# Sheet1.net
KiCad netlist of a schematic drawn in Altium Designer
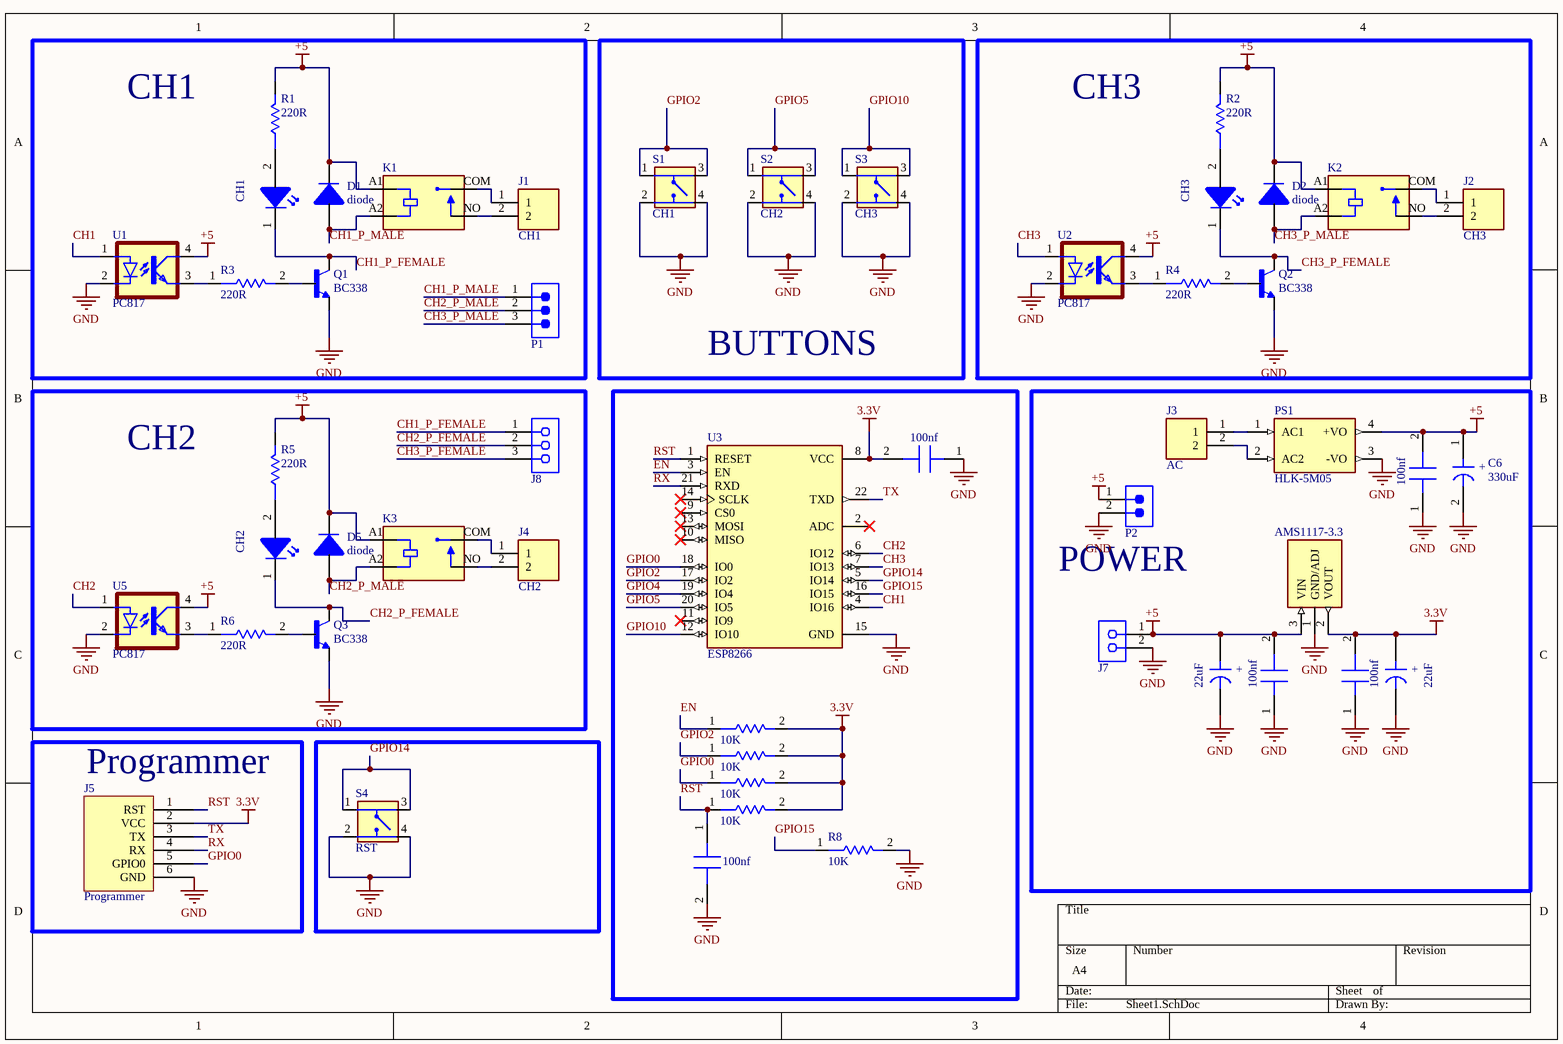
[diagram p0: Sheet1.SchDoc]

(export (version "E")
  (design (tool "Eeschema 10.0.6"))
  (components
    (comp (ref "C1")
      (value "100nf")
      (footprint "CL31B104KCFNNNE")
      (description "0.1 µF ±10% 100V Ceramic Capacitor X7R 1206 (3216 Metric)")
      (libsource (lib "Schlib1") (part "CL31B104KCFNNNE"))
    )
    (comp (ref "C4")
      (value "100nf")
      (footprint "CL31B104KCFNNNE")
      (description "0.1 µF ±10% 100V Ceramic Capacitor X7R 1206 (3216 Metric)")
      (libsource (lib "Schlib1") (part "CL31B104KCFNNNE"))
    )
    (comp (ref "C5")
      (value "100nf")
      (footprint "CL31B104KCFNNNE")
      (description "0.1 µF ±10% 100V Ceramic Capacitor X7R 1206 (3216 Metric)")
      (libsource (lib "Schlib1") (part "CL31B104KCFNNNE"))
    )
    (comp (ref "C6")
      (value "330uF")
      (footprint "UCL1V331MNL1GS")
      (description "330 µF 35 V Aluminum Electrolytic Capacitors Radial, Can - SMD 2000 Hrs @ 105°C")
      (libsource (lib "Schlib1") (part "UCL1V331MNL1GS"))
    )
    (comp (ref "C7")
      (value "100nf")
      (footprint "CL31B104KCFNNNE")
      (description "0.1 µF ±10% 100V Ceramic Capacitor X7R 1206 (3216 Metric)")
      (libsource (lib "Schlib1") (part "CL31B104KCFNNNE"))
    )
    (comp (ref "C8")
      (value "100nf")
      (footprint "CL31B104KCFNNNE")
      (description "0.1 µF ±10% 100V Ceramic Capacitor X7R 1206 (3216 Metric)")
      (libsource (lib "Schlib1") (part "CL31B104KCFNNNE"))
    )
    (comp (ref "C9")
      (value "22uF")
      (footprint "865060342002")
      (description "22 µF 16 V Aluminum Electrolytic Capacitors Radial, Can - SMD 2000 Hrs @ 105°C")
      (libsource (lib "Schlib1") (part "865060342002"))
    )
    (comp (ref "C10")
      (value "22uF")
      (footprint "865060342002")
      (description "22 µF 16 V Aluminum Electrolytic Capacitors Radial, Can - SMD 2000 Hrs @ 105°C")
      (libsource (lib "Schlib1") (part "865060342002"))
    )
    (comp (ref "D1")
      (value "diode")
      (footprint "1N4007W")
      (description "Diode 1000 V 1A Surface Mount SOD-123FL")
      (libsource (lib "Schlib1") (part "1N4007W"))
    )
    (comp (ref "D2")
      (value "diode")
      (footprint "1N4007W")
      (description "Diode 1000 V 1A Surface Mount SOD-123FL")
      (libsource (lib "Schlib1") (part "1N4007W"))
    )
    (comp (ref "D3")
      (value "CH1")
      (footprint "IN-S126ATR")
      (description "Red 622nm LED Indication - Discrete 2V 1206 (3216 Metric)")
      (libsource (lib "Schlib1") (part "IN-S126ATR"))
    )
    (comp (ref "D4")
      (value "CH3")
      (footprint "IN-S126ATR")
      (description "Red 622nm LED Indication - Discrete 2V 1206 (3216 Metric)")
      (libsource (lib "Schlib1") (part "IN-S126ATR"))
    )
    (comp (ref "D5")
      (value "diode")
      (footprint "1N4007W")
      (description "Diode 1000 V 1A Surface Mount SOD-123FL")
      (libsource (lib "Schlib1") (part "1N4007W"))
    )
    (comp (ref "D6")
      (value "CH2")
      (footprint "IN-S126ATR")
      (description "Red 622nm LED Indication - Discrete 2V 1206 (3216 Metric)")
      (libsource (lib "Schlib1") (part "IN-S126ATR"))
    )
    (comp (ref "J1")
      (value "CH1")
      (footprint "KF127-5.0-2P")
      (description "Connector, Terminal Block; Wire Receptacle; 2 Pos.; 16-30 AWG; 0.197 in. CL; Sid")
      (libsource (lib "Schlib1") (part "KF127-5.0-2P"))
    )
    (comp (ref "J2")
      (value "CH3")
      (footprint "KF127-5.0-2P")
      (description "Connector, Terminal Block; Wire Receptacle; 2 Pos.; 16-30 AWG; 0.197 in. CL; Sid")
      (libsource (lib "Schlib1") (part "KF127-5.0-2P"))
    )
    (comp (ref "J3")
      (value "AC")
      (footprint "KF127-5.0-2P")
      (description "Connector, Terminal Block; Wire Receptacle; 2 Pos.; 16-30 AWG; 0.197 in. CL; Sid")
      (libsource (lib "") (part "KF127-5.0-2P_1"))
    )
    (comp (ref "J4")
      (value "CH2")
      (footprint "KF127-5.0-2P")
      (description "Connector, Terminal Block; Wire Receptacle; 2 Pos.; 16-30 AWG; 0.197 in. CL; Sid")
      (libsource (lib "Schlib1") (part "KF127-5.0-2P"))
    )
    (comp (ref "J5")
      (value "Programmer")
      (footprint "PHT-106-XX-X-S")
      (description "6 pin male pin header")
      (libsource (lib "Schlib1") (part "PHT-106-XX-X-S"))
    )
    (comp (ref "J7")
      (value "61300211821")
      (footprint "61300211821")
      (description "WR-PHD Socket Header, THT, Vertical, pitch 2.54mm, 1 Row, 2P")
      (fields (field (name "MANUFACTURER") "Wurth Elektronik"))
      (libsource (lib "Altium_WR-PHD_rev24a") (part "61300211821"))
    )
    (comp (ref "J8")
      (value "61300311821")
      (footprint "61300311821")
      (description "WR-PHD Socket Header, THT, Vertical, pitch 2.54mm, 1 Row, 3P")
      (fields (field (name "MANUFACTURER") "Wurth Elektronik"))
      (libsource (lib "Altium_WR-PHD_rev24a") (part "61300311821"))
    )
    (comp (ref "K1")
      (value "PR8-5V-450-1A")
      (footprint "PR8-5V-450-1A")
      (description "18.2 x 10.2 x 15.5 mm, 5 V, 16 A, SPST (1 Form A), Power Relay")
      (libsource (lib "Schlib1") (part "PR8-5V-450-1A"))
    )
    (comp (ref "K2")
      (value "PR8-5V-450-1A")
      (footprint "PR8-5V-450-1A")
      (description "18.2 x 10.2 x 15.5 mm, 5 V, 16 A, SPST (1 Form A), Power Relay")
      (libsource (lib "Schlib1") (part "PR8-5V-450-1A"))
    )
    (comp (ref "K3")
      (value "PR8-5V-450-1A")
      (footprint "PR8-5V-450-1A")
      (description "18.2 x 10.2 x 15.5 mm, 5 V, 16 A, SPST (1 Form A), Power Relay")
      (libsource (lib "Schlib1") (part "PR8-5V-450-1A"))
    )
    (comp (ref "P1")
      (value "61300311121")
      (footprint "61300311121")
      (description "WR-PHD Pin Header, THT, Vertical, pitch 2.54mm, 1 Row, 3P")
      (fields (field (name "MANUFACTURER") "Wurth Elektronik"))
      (libsource (lib "Altium_WR-PHD_rev24a") (part "61300311121"))
    )
    (comp (ref "P2")
      (value "61300211121")
      (footprint "61300211121")
      (description "WR-PHD Pin Header, THT, Vertical, pitch 2.54mm, 1 Row, 2P")
      (fields (field (name "MANUFACTURER") "Wurth Elektronik"))
      (libsource (lib "Altium_WR-PHD_rev24a") (part "61300211121"))
    )
    (comp (ref "PS1")
      (value "HLK-5M05")
      (footprint "HLK-5M05")
      (description "AC DC 220V to 5V 5W 5Watt Isolated Switching Step-Down Power Supply Module Converter")
      (libsource (lib "Schlib1") (part "HLK-5M05"))
    )
    (comp (ref "Q1")
      (value "BC338")
      (footprint "BC338")
      (description "Bipolar (BJT) Transistor NPN 25 V 800 mA 100MHz 625 mW Through Hole TO-92-3")
      (libsource (lib "Schlib1") (part "BC338"))
    )
    (comp (ref "Q2")
      (value "BC338")
      (footprint "BC338")
      (description "Bipolar (BJT) Transistor NPN 25 V 800 mA 100MHz 625 mW Through Hole TO-92-3")
      (libsource (lib "Schlib1") (part "BC338"))
    )
    (comp (ref "Q3")
      (value "BC338")
      (footprint "BC338")
      (description "Bipolar (BJT) Transistor NPN 25 V 800 mA 100MHz 625 mW Through Hole TO-92-3")
      (libsource (lib "Schlib1") (part "BC338"))
    )
    (comp (ref "R1")
      (value "220R")
      (footprint "RMCF1206FT220R")
      (description "220 Ohms ±1% 0.25W, 1/4W Chip Resistor 1206 (3216 Metric) Automotive AEC-Q200 Thick Film")
      (libsource (lib "Schlib1") (part "RMCF1206FT220R"))
    )
    (comp (ref "R2")
      (value "220R")
      (footprint "RMCF1206FT220R")
      (description "220 Ohms ±1% 0.25W, 1/4W Chip Resistor 1206 (3216 Metric) Automotive AEC-Q200 Thick Film")
      (libsource (lib "Schlib1") (part "RMCF1206FT220R"))
    )
    (comp (ref "R3")
      (value "220R")
      (footprint "RMCF1206FT220R")
      (description "220 Ohms ±1% 0.25W, 1/4W Chip Resistor 1206 (3216 Metric) Automotive AEC-Q200 Thick Film")
      (libsource (lib "") (part "RMCF1206FT220R_1"))
    )
    (comp (ref "R4")
      (value "220R")
      (footprint "RMCF1206FT220R")
      (description "220 Ohms ±1% 0.25W, 1/4W Chip Resistor 1206 (3216 Metric) Automotive AEC-Q200 Thick Film")
      (libsource (lib "") (part "RMCF1206FT220R_1"))
    )
    (comp (ref "R5")
      (value "220R")
      (footprint "RMCF1206FT220R")
      (description "220 Ohms ±1% 0.25W, 1/4W Chip Resistor 1206 (3216 Metric) Automotive AEC-Q200 Thick Film")
      (libsource (lib "Schlib1") (part "RMCF1206FT220R"))
    )
    (comp (ref "R6")
      (value "220R")
      (footprint "RMCF1206FT220R")
      (description "220 Ohms ±1% 0.25W, 1/4W Chip Resistor 1206 (3216 Metric) Automotive AEC-Q200 Thick Film")
      (libsource (lib "") (part "RMCF1206FT220R_1"))
    )
    (comp (ref "R7")
      (value "10K")
      (footprint "RC1206FR-0710KL")
      (description "10 kOhms ±1% 0.25W, 1/4W Chip Resistor 1206 (3216 Metric) Moisture Resistant Thick Film")
      (libsource (lib "Schlib1") (part "RC1206FR-0710KL"))
    )
    (comp (ref "R8")
      (value "10K")
      (footprint "RC1206FR-0710KL")
      (description "10 kOhms ±1% 0.25W, 1/4W Chip Resistor 1206 (3216 Metric) Moisture Resistant Thick Film")
      (libsource (lib "Schlib1") (part "RC1206FR-0710KL"))
    )
    (comp (ref "R9")
      (value "10K")
      (footprint "RC1206FR-0710KL")
      (description "10 kOhms ±1% 0.25W, 1/4W Chip Resistor 1206 (3216 Metric) Moisture Resistant Thick Film")
      (libsource (lib "Schlib1") (part "RC1206FR-0710KL"))
    )
    (comp (ref "R11")
      (value "10K")
      (footprint "RC1206FR-0710KL")
      (description "10 kOhms ±1% 0.25W, 1/4W Chip Resistor 1206 (3216 Metric) Moisture Resistant Thick Film")
      (libsource (lib "Schlib1") (part "RC1206FR-0710KL"))
    )
    (comp (ref "R12")
      (value "10K")
      (footprint "RC1206FR-0710KL")
      (description "10 kOhms ±1% 0.25W, 1/4W Chip Resistor 1206 (3216 Metric) Moisture Resistant Thick Film")
      (libsource (lib "Schlib1") (part "RC1206FR-0710KL"))
    )
    (comp (ref "S1")
      (value "CH1")
      (footprint "FSM8JH")
      (description "Tactile Switch SPST-NO Top Actuated Through Hole")
      (libsource (lib "Schlib1") (part "FSM8JH"))
    )
    (comp (ref "S2")
      (value "CH2")
      (footprint "FSM8JH")
      (description "Tactile Switch SPST-NO Top Actuated Through Hole")
      (libsource (lib "Schlib1") (part "FSM8JH"))
    )
    (comp (ref "S3")
      (value "CH3")
      (footprint "FSM8JH")
      (description "Tactile Switch SPST-NO Top Actuated Through Hole")
      (libsource (lib "Schlib1") (part "FSM8JH"))
    )
    (comp (ref "S4")
      (value "RST")
      (footprint "FSM8JH")
      (description "Tactile Switch SPST-NO Top Actuated Through Hole")
      (libsource (lib "Schlib1") (part "FSM8JH"))
    )
    (comp (ref "U1")
      (value "PC817")
      (footprint "PC817X2NSZ9F")
      (description "Optoisolator Transistor Output 5000Vrms 1 Channel 4-DIP")
      (libsource (lib "Schlib1") (part "PC817X2NSZ9F"))
    )
    (comp (ref "U2")
      (value "PC817")
      (footprint "PC817X2NSZ9F")
      (description "Optoisolator Transistor Output 5000Vrms 1 Channel 4-DIP")
      (libsource (lib "Schlib1") (part "PC817X2NSZ9F"))
    )
    (comp (ref "U3")
      (value "ESP8266")
      (footprint "ESP8266-12-F")
      (libsource (lib "Schlib1") (part "ESP8266-12-F"))
    )
    (comp (ref "U4")
      (value "AMS1117-3.3")
      (footprint "AMS1117-3.3")
      (description "Sot223/Pkg 1-Amp 3.3-Volt Low Drop Out Voltage Regulatator")
      (libsource (lib "Schlib1") (part "AMS1117-3.3"))
    )
    (comp (ref "U5")
      (value "PC817")
      (footprint "PC817X2NSZ9F")
      (description "Optoisolator Transistor Output 5000Vrms 1 Channel 4-DIP")
      (libsource (lib "Schlib1") (part "PC817X2NSZ9F"))
    )
  )
  (nets
    (net (code "1") (name "+5") (class "Default")
      (node (ref "C5") (pin "2") (pinfunction "2_2") (pintype "passive"))
      (node (ref "C6") (pin "1") (pinfunction "1_1") (pintype "passive"))
      (node (ref "C7") (pin "2") (pinfunction "2_2") (pintype "passive"))
      (node (ref "C9") (pin "1") (pinfunction "1_1") (pintype "passive"))
      (node (ref "D1") (pin "1") (pinfunction "1_1") (pintype "passive"))
      (node (ref "D2") (pin "1") (pinfunction "1_1") (pintype "passive"))
      (node (ref "D5") (pin "1") (pinfunction "1_1") (pintype "passive"))
      (node (ref "J7") (pin "1") (pinfunction "1_1") (pintype "passive"))
      (node (ref "K1") (pin "A1") (pinfunction "COIL1_A1") (pintype "passive"))
      (node (ref "K2") (pin "A1") (pinfunction "COIL1_A1") (pintype "passive"))
      (node (ref "K3") (pin "A1") (pinfunction "COIL1_A1") (pintype "passive"))
      (node (ref "P2") (pin "1") (pinfunction "1_1") (pintype "passive"))
      (node (ref "PS1") (pin "4") (pinfunction "+VO_4") (pintype "output"))
      (node (ref "R1") (pin "2") (pinfunction "2_2") (pintype "passive"))
      (node (ref "R2") (pin "2") (pinfunction "2_2") (pintype "passive"))
      (node (ref "R5") (pin "2") (pinfunction "2_2") (pintype "passive"))
      (node (ref "U1") (pin "4") (pinfunction "COL_4") (pintype "passive"))
      (node (ref "U2") (pin "4") (pinfunction "COL_4") (pintype "passive"))
      (node (ref "U4") (pin "3") (pinfunction "VIN_3") (pintype "input"))
      (node (ref "U5") (pin "4") (pinfunction "COL_4") (pintype "passive"))
    )
    (net (code "2") (name "/CH1") (class "Default")
      (node (ref "U1") (pin "1") (pinfunction "A_1") (pintype "passive"))
      (node (ref "U3") (pin "4") (pinfunction "IO16_4") (pintype "bidirectional"))
    )
    (net (code "3") (name "/CH1_P_FEMALE") (class "Default")
      (node (ref "D3") (pin "1") (pinfunction "1_1") (pintype "passive"))
      (node (ref "J8") (pin "1") (pinfunction "1_1") (pintype "passive"))
      (node (ref "Q1") (pin "C") (pinfunction "C_C") (pintype "passive"))
    )
    (net (code "4") (name "/CH1_P_MALE") (class "Default")
      (node (ref "D1") (pin "2") (pinfunction "12_2") (pintype "passive"))
      (node (ref "K1") (pin "A2") (pinfunction "COIL2_A2") (pintype "passive"))
      (node (ref "P1") (pin "1") (pinfunction "1_1") (pintype "passive"))
    )
    (net (code "5") (name "/CH2") (class "Default")
      (node (ref "U3") (pin "6") (pinfunction "IO12_6") (pintype "bidirectional"))
      (node (ref "U5") (pin "1") (pinfunction "A_1") (pintype "passive"))
    )
    (net (code "6") (name "/CH2_P_FEMALE") (class "Default")
      (node (ref "D6") (pin "1") (pinfunction "1_1") (pintype "passive"))
      (node (ref "J8") (pin "2") (pinfunction "2_2") (pintype "passive"))
      (node (ref "Q3") (pin "C") (pinfunction "C_C") (pintype "passive"))
    )
    (net (code "7") (name "/CH2_P_MALE") (class "Default")
      (node (ref "D5") (pin "2") (pinfunction "12_2") (pintype "passive"))
      (node (ref "K3") (pin "A2") (pinfunction "COIL2_A2") (pintype "passive"))
      (node (ref "P1") (pin "2") (pinfunction "2_2") (pintype "passive"))
    )
    (net (code "8") (name "/CH3") (class "Default")
      (node (ref "U2") (pin "1") (pinfunction "A_1") (pintype "passive"))
      (node (ref "U3") (pin "7") (pinfunction "IO13_7") (pintype "bidirectional"))
    )
    (net (code "9") (name "/CH3_P_FEMALE") (class "Default")
      (node (ref "D4") (pin "1") (pinfunction "1_1") (pintype "passive"))
      (node (ref "J8") (pin "3") (pinfunction "3_3") (pintype "passive"))
      (node (ref "Q2") (pin "C") (pinfunction "C_C") (pintype "passive"))
    )
    (net (code "10") (name "/CH3_P_MALE") (class "Default")
      (node (ref "D2") (pin "2") (pinfunction "12_2") (pintype "passive"))
      (node (ref "K2") (pin "A2") (pinfunction "COIL2_A2") (pintype "passive"))
      (node (ref "P1") (pin "3") (pinfunction "3_3") (pintype "passive"))
    )
    (net (code "11") (name "/EN") (class "Default")
      (node (ref "R7") (pin "1") (pinfunction "1_1") (pintype "passive"))
      (node (ref "U3") (pin "3") (pinfunction "EN_3") (pintype "input"))
    )
    (net (code "12") (name "/GPIO0") (class "Default")
      (node (ref "J5") (pin "5") (pinfunction "GPIO0_5") (pintype "passive"))
      (node (ref "R9") (pin "1") (pinfunction "1_1") (pintype "passive"))
      (node (ref "U3") (pin "18") (pinfunction "IO0_18") (pintype "bidirectional"))
    )
    (net (code "13") (name "/GPIO2") (class "Default")
      (node (ref "R11") (pin "1") (pinfunction "1_1") (pintype "passive"))
      (node (ref "S1") (pin "1") (pinfunction "1_1") (pintype "passive"))
      (node (ref "S1") (pin "3") (pinfunction "3_3") (pintype "passive"))
      (node (ref "U3") (pin "17") (pinfunction "IO2_17") (pintype "bidirectional"))
    )
    (net (code "14") (name "/GPIO4") (class "Default")
      (node (ref "U3") (pin "19") (pinfunction "IO4_19") (pintype "bidirectional"))
    )
    (net (code "15") (name "/GPIO5") (class "Default")
      (node (ref "S2") (pin "1") (pinfunction "1_1") (pintype "passive"))
      (node (ref "S2") (pin "3") (pinfunction "3_3") (pintype "passive"))
      (node (ref "U3") (pin "20") (pinfunction "IO5_20") (pintype "bidirectional"))
    )
    (net (code "16") (name "/GPIO10") (class "Default")
      (node (ref "S3") (pin "1") (pinfunction "1_1") (pintype "passive"))
      (node (ref "S3") (pin "3") (pinfunction "3_3") (pintype "passive"))
      (node (ref "U3") (pin "12") (pinfunction "IO10_12") (pintype "bidirectional"))
    )
    (net (code "17") (name "/GPIO14") (class "Default")
      (node (ref "S4") (pin "1") (pinfunction "1_1") (pintype "passive"))
      (node (ref "S4") (pin "3") (pinfunction "3_3") (pintype "passive"))
      (node (ref "U3") (pin "5") (pinfunction "IO14_5") (pintype "bidirectional"))
    )
    (net (code "18") (name "/GPIO15") (class "Default")
      (node (ref "R8") (pin "1") (pinfunction "1_1") (pintype "passive"))
      (node (ref "U3") (pin "16") (pinfunction "IO15_16") (pintype "bidirectional"))
    )
    (net (code "19") (name "/RST") (class "Default")
      (node (ref "C1") (pin "1") (pinfunction "1_1") (pintype "passive"))
      (node (ref "J5") (pin "1") (pinfunction "RST_1") (pintype "passive"))
      (node (ref "R12") (pin "1") (pinfunction "1_1") (pintype "passive"))
      (node (ref "U3") (pin "1") (pinfunction "RESET_1") (pintype "input"))
    )
    (net (code "20") (name "/RX") (class "Default")
      (node (ref "J5") (pin "4") (pinfunction "RX_4") (pintype "passive"))
      (node (ref "U3") (pin "21") (pinfunction "RXD_21") (pintype "input"))
    )
    (net (code "21") (name "/TX") (class "Default")
      (node (ref "J5") (pin "3") (pinfunction "TX_3") (pintype "passive"))
      (node (ref "U3") (pin "22") (pinfunction "TXD_22") (pintype "output"))
    )
    (net (code "22") (name "3.3V") (class "Default")
      (node (ref "C10") (pin "1") (pinfunction "1_1") (pintype "passive"))
      (node (ref "C4") (pin "2") (pinfunction "2_2") (pintype "passive"))
      (node (ref "C8") (pin "2") (pinfunction "2_2") (pintype "passive"))
      (node (ref "J5") (pin "2") (pinfunction "VCC_2") (pintype "passive"))
      (node (ref "R11") (pin "2") (pinfunction "2_2") (pintype "passive"))
      (node (ref "R12") (pin "2") (pinfunction "2_2") (pintype "passive"))
      (node (ref "R7") (pin "2") (pinfunction "2_2") (pintype "passive"))
      (node (ref "R9") (pin "2") (pinfunction "2_2") (pintype "passive"))
      (node (ref "U3") (pin "8") (pinfunction "VCC_8") (pintype "power_in"))
      (node (ref "U4") (pin "2") (pinfunction "VOUT_2") (pintype "output"))
    )
    (net (code "23") (name "GND") (class "Default")
      (node (ref "C1") (pin "2") (pinfunction "2_2") (pintype "passive"))
      (node (ref "C10") (pin "2") (pinfunction "2_2") (pintype "passive"))
      (node (ref "C4") (pin "1") (pinfunction "1_1") (pintype "passive"))
      (node (ref "C5") (pin "1") (pinfunction "1_1") (pintype "passive"))
      (node (ref "C6") (pin "2") (pinfunction "2_2") (pintype "passive"))
      (node (ref "C7") (pin "1") (pinfunction "1_1") (pintype "passive"))
      (node (ref "C8") (pin "1") (pinfunction "1_1") (pintype "passive"))
      (node (ref "C9") (pin "2") (pinfunction "2_2") (pintype "passive"))
      (node (ref "J5") (pin "6") (pinfunction "GND_6") (pintype "passive"))
      (node (ref "J7") (pin "2") (pinfunction "2_2") (pintype "passive"))
      (node (ref "P2") (pin "2") (pinfunction "2_2") (pintype "passive"))
      (node (ref "PS1") (pin "3") (pinfunction "-VO_3") (pintype "output"))
      (node (ref "Q1") (pin "E") (pinfunction "E_E") (pintype "passive"))
      (node (ref "Q2") (pin "E") (pinfunction "E_E") (pintype "passive"))
      (node (ref "Q3") (pin "E") (pinfunction "E_E") (pintype "passive"))
      (node (ref "R8") (pin "2") (pinfunction "2_2") (pintype "passive"))
      (node (ref "S1") (pin "2") (pinfunction "2_2") (pintype "passive"))
      (node (ref "S1") (pin "4") (pinfunction "4_4") (pintype "passive"))
      (node (ref "S2") (pin "2") (pinfunction "2_2") (pintype "passive"))
      (node (ref "S2") (pin "4") (pinfunction "4_4") (pintype "passive"))
      (node (ref "S3") (pin "2") (pinfunction "2_2") (pintype "passive"))
      (node (ref "S3") (pin "4") (pinfunction "4_4") (pintype "passive"))
      (node (ref "S4") (pin "2") (pinfunction "2_2") (pintype "passive"))
      (node (ref "S4") (pin "4") (pinfunction "4_4") (pintype "passive"))
      (node (ref "U1") (pin "2") (pinfunction "C_2") (pintype "passive"))
      (node (ref "U2") (pin "2") (pinfunction "C_2") (pintype "passive"))
      (node (ref "U3") (pin "15") (pinfunction "GND_15") (pintype "power_in"))
      (node (ref "U4") (pin "1") (pinfunction "GND/ADJ_1") (pintype "power_in"))
      (node (ref "U5") (pin "2") (pinfunction "C_2") (pintype "passive"))
    )
    (net (code "24") (name "Net-(D3-12)") (class "Default")
      (node (ref "D3") (pin "2") (pinfunction "12_2") (pintype "passive"))
      (node (ref "R1") (pin "1") (pinfunction "1_1") (pintype "passive"))
    )
    (net (code "25") (name "Net-(D4-12)") (class "Default")
      (node (ref "D4") (pin "2") (pinfunction "12_2") (pintype "passive"))
      (node (ref "R2") (pin "1") (pinfunction "1_1") (pintype "passive"))
    )
    (net (code "26") (name "Net-(D6-12)") (class "Default")
      (node (ref "D6") (pin "2") (pinfunction "12_2") (pintype "passive"))
      (node (ref "R5") (pin "1") (pinfunction "1_1") (pintype "passive"))
    )
    (net (code "27") (name "Net-(J1-Pad1)") (class "Default")
      (node (ref "J1") (pin "1") (pinfunction "1_1") (pintype "passive"))
      (node (ref "K1") (pin "COM") (pinfunction "COM_COM") (pintype "passive"))
    )
    (net (code "28") (name "Net-(J1-Pad2)") (class "Default")
      (node (ref "J1") (pin "2") (pinfunction "2_2") (pintype "passive"))
      (node (ref "K1") (pin "NO") (pinfunction "NO_NO") (pintype "passive"))
    )
    (net (code "29") (name "Net-(J2-Pad1)") (class "Default")
      (node (ref "J2") (pin "1") (pinfunction "1_1") (pintype "passive"))
      (node (ref "K2") (pin "COM") (pinfunction "COM_COM") (pintype "passive"))
    )
    (net (code "30") (name "Net-(J2-Pad2)") (class "Default")
      (node (ref "J2") (pin "2") (pinfunction "2_2") (pintype "passive"))
      (node (ref "K2") (pin "NO") (pinfunction "NO_NO") (pintype "passive"))
    )
    (net (code "31") (name "Net-(J4-Pad1)") (class "Default")
      (node (ref "J4") (pin "1") (pinfunction "1_1") (pintype "passive"))
      (node (ref "K3") (pin "COM") (pinfunction "COM_COM") (pintype "passive"))
    )
    (net (code "32") (name "Net-(J4-Pad2)") (class "Default")
      (node (ref "J4") (pin "2") (pinfunction "2_2") (pintype "passive"))
      (node (ref "K3") (pin "NO") (pinfunction "NO_NO") (pintype "passive"))
    )
    (net (code "33") (name "Net-(PS1-AC1)") (class "Default")
      (node (ref "J3") (pin "1") (pinfunction "1_1") (pintype "passive"))
      (node (ref "PS1") (pin "1") (pinfunction "AC1_1") (pintype "input"))
    )
    (net (code "34") (name "Net-(PS1-AC2)") (class "Default")
      (node (ref "J3") (pin "2") (pinfunction "2_2") (pintype "passive"))
      (node (ref "PS1") (pin "2") (pinfunction "AC2_2") (pintype "input"))
    )
    (net (code "35") (name "Net-(Q1-PadB)") (class "Default")
      (node (ref "Q1") (pin "B") (pinfunction "B_B") (pintype "passive"))
      (node (ref "R3") (pin "2") (pinfunction "2_2") (pintype "passive"))
    )
    (net (code "36") (name "Net-(Q2-PadB)") (class "Default")
      (node (ref "Q2") (pin "B") (pinfunction "B_B") (pintype "passive"))
      (node (ref "R4") (pin "2") (pinfunction "2_2") (pintype "passive"))
    )
    (net (code "37") (name "Net-(Q3-PadB)") (class "Default")
      (node (ref "Q3") (pin "B") (pinfunction "B_B") (pintype "passive"))
      (node (ref "R6") (pin "2") (pinfunction "2_2") (pintype "passive"))
    )
    (net (code "38") (name "Net-(U1-EMIT)") (class "Default")
      (node (ref "R3") (pin "1") (pinfunction "1_1") (pintype "passive"))
      (node (ref "U1") (pin "3") (pinfunction "EMIT_3") (pintype "passive"))
    )
    (net (code "39") (name "Net-(U2-EMIT)") (class "Default")
      (node (ref "R4") (pin "1") (pinfunction "1_1") (pintype "passive"))
      (node (ref "U2") (pin "3") (pinfunction "EMIT_3") (pintype "passive"))
    )
    (net (code "40") (name "Net-(U5-EMIT)") (class "Default")
      (node (ref "R6") (pin "1") (pinfunction "1_1") (pintype "passive"))
      (node (ref "U5") (pin "3") (pinfunction "EMIT_3") (pintype "passive"))
    )
    (net (code "41") (name "unconnected-(U3-ADC-Pad2)") (class "Default")
      (node (ref "U3") (pin "2") (pinfunction "ADC_2") (pintype "passive+no_connect"))
    )
    (net (code "42") (name "unconnected-(U3-CS0-Pad9)") (class "Default")
      (node (ref "U3") (pin "9") (pinfunction "CS0_9") (pintype "input+no_connect"))
    )
    (net (code "43") (name "unconnected-(U3-IO9-Pad11)") (class "Default")
      (node (ref "U3") (pin "11") (pinfunction "IO9_11") (pintype "bidirectional+no_connect"))
    )
    (net (code "44") (name "unconnected-(U3-MISO-Pad10)") (class "Default")
      (node (ref "U3") (pin "10") (pinfunction "MISO_10") (pintype "bidirectional+no_connect"))
    )
    (net (code "45") (name "unconnected-(U3-MOSI-Pad13)") (class "Default")
      (node (ref "U3") (pin "13") (pinfunction "MOSI_13") (pintype "bidirectional+no_connect"))
    )
    (net (code "46") (name "unconnected-(U3-SCLK-Pad14)") (class "Default")
      (node (ref "U3") (pin "14") (pinfunction "SCLK_14") (pintype "input+no_connect"))
    )
  )
)
